# dongle.net
KiCad netlist of a schematic drawn in EAGLE
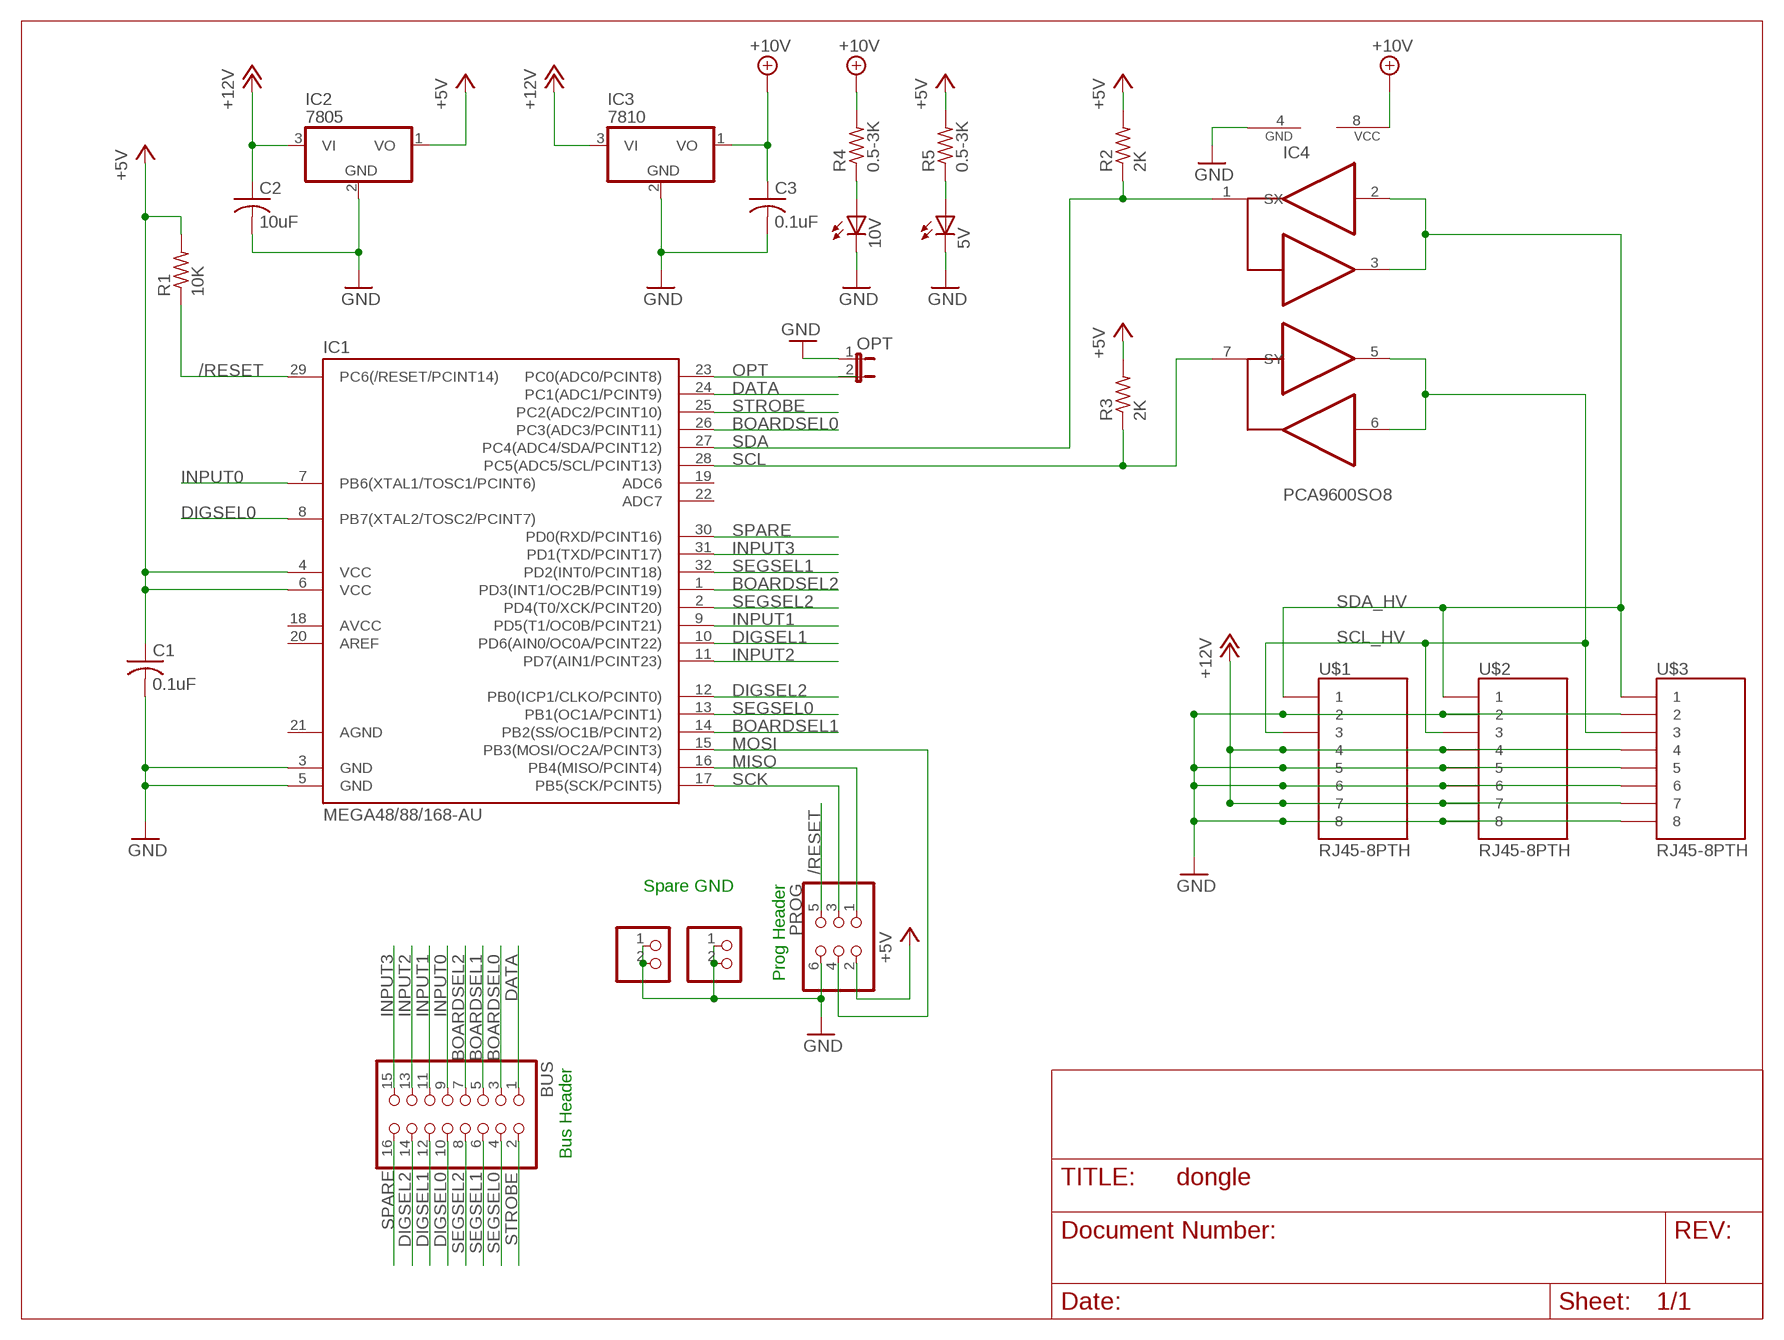
[diagram p0: schematic, sheet 1]

(export (version "E")
  (design (tool "Eeschema 10.0.6"))
  (components
    (comp (ref "5V")
      (value "LED3MM")
      (footprint "eagle-import:LED3MM")
      (libsource (lib "eagle-import") (part "LED3MM"))
    )
    (comp (ref "10V")
      (value "LED3MM")
      (footprint "eagle-import:LED3MM")
      (libsource (lib "eagle-import") (part "LED3MM"))
    )
    (comp (ref "BUS")
      (value "PINHD-2X8")
      (footprint "eagle-import:2X08")
      (libsource (lib "eagle-import") (part "PINHD-2X8"))
    )
    (comp (ref "C1")
      (value "0.1uF")
      (footprint "eagle-import:C025-025X050")
      (libsource (lib "eagle-import") (part "C-US025-025X050"))
    )
    (comp (ref "C2")
      (value "10uF")
      (footprint "eagle-import:C025-025X050")
      (libsource (lib "eagle-import") (part "C-US025-025X050"))
    )
    (comp (ref "C3")
      (value "0.1uF")
      (footprint "eagle-import:C025-025X050")
      (libsource (lib "eagle-import") (part "C-US025-025X050"))
    )
    (comp (ref "GROUND1")
      (value "PINHD-1X2")
      (footprint "eagle-import:1X02")
      (libsource (lib "eagle-import") (part "PINHD-1X2"))
    )
    (comp (ref "GROUND2")
      (value "PINHD-1X2")
      (footprint "eagle-import:1X02")
      (libsource (lib "eagle-import") (part "PINHD-1X2"))
    )
    (comp (ref "IC1")
      (value "MEGA48/88/168-AU")
      (footprint "eagle-import:TQFP32-08")
      (libsource (lib "eagle-import") (part "MEGA48/88/168-AU"))
    )
    (comp (ref "IC2")
      (value "7805")
      (footprint "eagle-import:TO92")
      (libsource (lib "eagle-import") (part "78ZL05"))
    )
    (comp (ref "IC3")
      (value "7810")
      (footprint "eagle-import:TO92")
      (libsource (lib "eagle-import") (part "78ZL05"))
    )
    (comp (ref "IC4")
      (value "PCA9600SO8")
      (footprint "eagle-import:SO08")
      (libsource (lib "eagle-import") (part "PCA9600SO8"))
    )
    (comp (ref "OPT")
      (value "JUMPER-2PTH")
      (footprint "eagle-import:1X02")
      (libsource (lib "eagle-import") (part "JUMPER-2PTH"))
    )
    (comp (ref "PROG")
      (value "PINHD-2X3")
      (footprint "eagle-import:2X03")
      (libsource (lib "eagle-import") (part "PINHD-2X3"))
    )
    (comp (ref "R1")
      (value "10K")
      (footprint "eagle-import:0204_5")
      (libsource (lib "eagle-import") (part "R-US_0204/5"))
    )
    (comp (ref "R2")
      (value "2K")
      (footprint "eagle-import:0204_5")
      (libsource (lib "eagle-import") (part "R-US_0204/5"))
    )
    (comp (ref "R3")
      (value "2K")
      (footprint "eagle-import:0204_5")
      (libsource (lib "eagle-import") (part "R-US_0204/5"))
    )
    (comp (ref "R4")
      (value "0.5-3K")
      (footprint "eagle-import:0204_5")
      (libsource (lib "eagle-import") (part "R-US_0204/5"))
    )
    (comp (ref "R5")
      (value "0.5-3K")
      (footprint "eagle-import:0204_5")
      (libsource (lib "eagle-import") (part "R-US_0204/5"))
    )
    (comp (ref "U$1")
      (value "RJ45-8PTH")
      (footprint "eagle-import:RJ45-8")
      (libsource (lib "eagle-import") (part "RJ45-8PTH"))
    )
    (comp (ref "U$2")
      (value "RJ45-8PTH")
      (footprint "eagle-import:RJ45-8")
      (libsource (lib "eagle-import") (part "RJ45-8PTH"))
    )
    (comp (ref "U$3")
      (value "RJ45-8PTH")
      (footprint "eagle-import:RJ45-8")
      (libsource (lib "eagle-import") (part "RJ45-8PTH"))
    )
  )
  (nets
    (net (code "1") (name "+5V") (class "Default")
      (node (ref "C1") (pin "1") (pinfunction "1_1") (pintype "passive"))
      (node (ref "IC1") (pin "4") (pinfunction "VCC_4") (pintype "power_in"))
      (node (ref "IC1") (pin "6") (pinfunction "VCC_6") (pintype "power_in"))
      (node (ref "IC2") (pin "1") (pinfunction "VO_1") (pintype "passive"))
      (node (ref "PROG") (pin "2") (pinfunction "2_2") (pintype "passive"))
      (node (ref "R1") (pin "2") (pinfunction "2_2") (pintype "passive"))
      (node (ref "R2") (pin "2") (pinfunction "2_2") (pintype "passive"))
      (node (ref "R3") (pin "2") (pinfunction "2_2") (pintype "passive"))
      (node (ref "R5") (pin "2") (pinfunction "2_2") (pintype "passive"))
    )
    (net (code "2") (name "+10V") (class "Default")
      (node (ref "C3") (pin "1") (pinfunction "1_1") (pintype "passive"))
      (node (ref "IC3") (pin "1") (pinfunction "VO_1") (pintype "passive"))
      (node (ref "IC4") (pin "8") (pinfunction "VCC_8") (pintype "power_in"))
      (node (ref "R4") (pin "2") (pinfunction "2_2") (pintype "passive"))
    )
    (net (code "3") (name "+12V") (class "Default")
      (node (ref "C2") (pin "1") (pinfunction "1_1") (pintype "passive"))
      (node (ref "IC2") (pin "3") (pinfunction "VI_3") (pintype "input"))
      (node (ref "IC3") (pin "3") (pinfunction "VI_3") (pintype "input"))
      (node (ref "U$1") (pin "4") (pinfunction "4_4") (pintype "bidirectional"))
      (node (ref "U$1") (pin "7") (pinfunction "7_7") (pintype "bidirectional"))
      (node (ref "U$2") (pin "4") (pinfunction "4_4") (pintype "bidirectional"))
      (node (ref "U$2") (pin "7") (pinfunction "7_7") (pintype "bidirectional"))
      (node (ref "U$3") (pin "4") (pinfunction "4_4") (pintype "bidirectional"))
      (node (ref "U$3") (pin "7") (pinfunction "7_7") (pintype "bidirectional"))
    )
    (net (code "4") (name "/AGND") (class "Default")
      (node (ref "IC1") (pin "21") (pinfunction "AGND_21") (pintype "power_in"))
    )
    (net (code "5") (name "/BOARDSEL0") (class "Default")
      (node (ref "BUS") (pin "3") (pinfunction "3_3") (pintype "passive"))
      (node (ref "IC1") (pin "26") (pinfunction "PC3(ADC3/PCINT11)_26") (pintype "bidirectional"))
    )
    (net (code "6") (name "/BOARDSEL1") (class "Default")
      (node (ref "BUS") (pin "5") (pinfunction "5_5") (pintype "passive"))
      (node (ref "IC1") (pin "14") (pinfunction "PB2(SS/OC1B/PCINT2)_14") (pintype "bidirectional"))
    )
    (net (code "7") (name "/BOARDSEL2") (class "Default")
      (node (ref "BUS") (pin "7") (pinfunction "7_7") (pintype "passive"))
      (node (ref "IC1") (pin "1") (pinfunction "PD3(INT1/OC2B/PCINT19)_1") (pintype "bidirectional"))
    )
    (net (code "8") (name "/DATA") (class "Default")
      (node (ref "BUS") (pin "1") (pinfunction "1_1") (pintype "passive"))
      (node (ref "IC1") (pin "24") (pinfunction "PC1(ADC1/PCINT9)_24") (pintype "bidirectional"))
    )
    (net (code "9") (name "/DIGSEL0") (class "Default")
      (node (ref "BUS") (pin "10") (pinfunction "10_10") (pintype "passive"))
      (node (ref "IC1") (pin "8") (pinfunction "PB7(XTAL2/TOSC2/PCINT7)_8") (pintype "bidirectional"))
    )
    (net (code "10") (name "/DIGSEL1") (class "Default")
      (node (ref "BUS") (pin "12") (pinfunction "12_12") (pintype "passive"))
      (node (ref "IC1") (pin "10") (pinfunction "PD6(AIN0/OC0A/PCINT22)_10") (pintype "bidirectional"))
    )
    (net (code "11") (name "/DIGSEL2") (class "Default")
      (node (ref "BUS") (pin "14") (pinfunction "14_14") (pintype "passive"))
      (node (ref "IC1") (pin "12") (pinfunction "PB0(ICP1/CLKO/PCINT0)_12") (pintype "bidirectional"))
    )
    (net (code "12") (name "/INPUT0") (class "Default")
      (node (ref "BUS") (pin "9") (pinfunction "9_9") (pintype "passive"))
      (node (ref "IC1") (pin "7") (pinfunction "PB6(XTAL1/TOSC1/PCINT6)_7") (pintype "bidirectional"))
    )
    (net (code "13") (name "/INPUT1") (class "Default")
      (node (ref "BUS") (pin "11") (pinfunction "11_11") (pintype "passive"))
      (node (ref "IC1") (pin "9") (pinfunction "PD5(T1/OC0B/PCINT21)_9") (pintype "bidirectional"))
    )
    (net (code "14") (name "/INPUT2") (class "Default")
      (node (ref "BUS") (pin "13") (pinfunction "13_13") (pintype "passive"))
      (node (ref "IC1") (pin "11") (pinfunction "PD7(AIN1/PCINT23)_11") (pintype "bidirectional"))
    )
    (net (code "15") (name "/INPUT3") (class "Default")
      (node (ref "BUS") (pin "15") (pinfunction "15_15") (pintype "passive"))
      (node (ref "IC1") (pin "31") (pinfunction "PD1(TXD/PCINT17)_31") (pintype "bidirectional"))
    )
    (net (code "16") (name "/MISO") (class "Default")
      (node (ref "IC1") (pin "16") (pinfunction "PB4(MISO/PCINT4)_16") (pintype "bidirectional"))
      (node (ref "PROG") (pin "1") (pinfunction "1_1") (pintype "passive"))
    )
    (net (code "17") (name "/MOSI") (class "Default")
      (node (ref "IC1") (pin "15") (pinfunction "PB3(MOSI/OC2A/PCINT3)_15") (pintype "bidirectional"))
      (node (ref "PROG") (pin "4") (pinfunction "4_4") (pintype "passive"))
    )
    (net (code "18") (name "/OPT") (class "Default")
      (node (ref "IC1") (pin "23") (pinfunction "PC0(ADC0/PCINT8)_23") (pintype "bidirectional"))
      (node (ref "OPT") (pin "2") (pinfunction "2_2") (pintype "passive"))
    )
    (net (code "19") (name "/SCK") (class "Default")
      (node (ref "IC1") (pin "17") (pinfunction "PB5(SCK/PCINT5)_17") (pintype "bidirectional"))
      (node (ref "PROG") (pin "3") (pinfunction "3_3") (pintype "passive"))
    )
    (net (code "20") (name "/SCL") (class "Default")
      (node (ref "IC1") (pin "28") (pinfunction "PC5(ADC5/SCL/PCINT13)_28") (pintype "bidirectional"))
      (node (ref "IC4") (pin "7") (pinfunction "SY_7") (pintype "bidirectional"))
      (node (ref "R3") (pin "1") (pinfunction "1_1") (pintype "passive"))
    )
    (net (code "21") (name "/SCL_HV") (class "Default")
      (node (ref "IC4") (pin "5") (pinfunction "TY_5") (pintype "output"))
      (node (ref "IC4") (pin "6") (pinfunction "RY_6") (pintype "input"))
      (node (ref "U$1") (pin "3") (pinfunction "3_3") (pintype "bidirectional"))
      (node (ref "U$2") (pin "3") (pinfunction "3_3") (pintype "bidirectional"))
      (node (ref "U$3") (pin "3") (pinfunction "3_3") (pintype "bidirectional"))
    )
    (net (code "22") (name "/SDA") (class "Default")
      (node (ref "IC1") (pin "27") (pinfunction "PC4(ADC4/SDA/PCINT12)_27") (pintype "bidirectional"))
      (node (ref "IC4") (pin "1") (pinfunction "SX_1") (pintype "bidirectional"))
      (node (ref "R2") (pin "1") (pinfunction "1_1") (pintype "passive"))
    )
    (net (code "23") (name "/SDA_HV") (class "Default")
      (node (ref "IC4") (pin "2") (pinfunction "RX_2") (pintype "input"))
      (node (ref "IC4") (pin "3") (pinfunction "TX_3") (pintype "output"))
      (node (ref "U$1") (pin "1") (pinfunction "1_1") (pintype "bidirectional"))
      (node (ref "U$2") (pin "1") (pinfunction "1_1") (pintype "bidirectional"))
      (node (ref "U$3") (pin "1") (pinfunction "1_1") (pintype "bidirectional"))
    )
    (net (code "24") (name "/SEGSEL0") (class "Default")
      (node (ref "BUS") (pin "4") (pinfunction "4_4") (pintype "passive"))
      (node (ref "IC1") (pin "13") (pinfunction "PB1(OC1A/PCINT1)_13") (pintype "bidirectional"))
    )
    (net (code "25") (name "/SEGSEL1") (class "Default")
      (node (ref "BUS") (pin "6") (pinfunction "6_6") (pintype "passive"))
      (node (ref "IC1") (pin "32") (pinfunction "PD2(INT0/PCINT18)_32") (pintype "bidirectional"))
    )
    (net (code "26") (name "/SEGSEL2") (class "Default")
      (node (ref "BUS") (pin "8") (pinfunction "8_8") (pintype "passive"))
      (node (ref "IC1") (pin "2") (pinfunction "PD4(T0/XCK/PCINT20)_2") (pintype "bidirectional"))
    )
    (net (code "27") (name "/SPARE") (class "Default")
      (node (ref "BUS") (pin "16") (pinfunction "16_16") (pintype "passive"))
      (node (ref "IC1") (pin "30") (pinfunction "PD0(RXD/PCINT16)_30") (pintype "bidirectional"))
    )
    (net (code "28") (name "/STROBE") (class "Default")
      (node (ref "BUS") (pin "2") (pinfunction "2_2") (pintype "passive"))
      (node (ref "IC1") (pin "25") (pinfunction "PC2(ADC2/PCINT10)_25") (pintype "bidirectional"))
    )
    (net (code "29") (name "/{slash}RESET") (class "Default")
      (node (ref "IC1") (pin "29") (pinfunction "PC6(/RESET/PCINT14)_29") (pintype "bidirectional"))
      (node (ref "PROG") (pin "5") (pinfunction "5_5") (pintype "passive"))
      (node (ref "R1") (pin "1") (pinfunction "1_1") (pintype "passive"))
    )
    (net (code "30") (name "GND") (class "Default")
      (node (ref "10V") (pin "K") (pinfunction "C_K") (pintype "passive"))
      (node (ref "5V") (pin "K") (pinfunction "C_K") (pintype "passive"))
      (node (ref "C1") (pin "2") (pinfunction "2_2") (pintype "passive"))
      (node (ref "C2") (pin "2") (pinfunction "2_2") (pintype "passive"))
      (node (ref "C3") (pin "2") (pinfunction "2_2") (pintype "passive"))
      (node (ref "GROUND1") (pin "1") (pinfunction "1_1") (pintype "passive"))
      (node (ref "GROUND1") (pin "2") (pinfunction "2_2") (pintype "passive"))
      (node (ref "GROUND2") (pin "1") (pinfunction "1_1") (pintype "passive"))
      (node (ref "GROUND2") (pin "2") (pinfunction "2_2") (pintype "passive"))
      (node (ref "IC1") (pin "3") (pinfunction "GND_3") (pintype "power_in"))
      (node (ref "IC1") (pin "5") (pinfunction "GND_5") (pintype "power_in"))
      (node (ref "IC2") (pin "2") (pinfunction "GND_2") (pintype "passive"))
      (node (ref "IC3") (pin "2") (pinfunction "GND_2") (pintype "passive"))
      (node (ref "IC4") (pin "4") (pinfunction "GND_4") (pintype "power_in"))
      (node (ref "OPT") (pin "1") (pinfunction "1_1") (pintype "passive"))
      (node (ref "PROG") (pin "6") (pinfunction "6_6") (pintype "passive"))
      (node (ref "U$1") (pin "2") (pinfunction "2_2") (pintype "bidirectional"))
      (node (ref "U$1") (pin "5") (pinfunction "5_5") (pintype "bidirectional"))
      (node (ref "U$1") (pin "6") (pinfunction "6_6") (pintype "bidirectional"))
      (node (ref "U$1") (pin "8") (pinfunction "8_8") (pintype "bidirectional"))
      (node (ref "U$2") (pin "2") (pinfunction "2_2") (pintype "bidirectional"))
      (node (ref "U$2") (pin "5") (pinfunction "5_5") (pintype "bidirectional"))
      (node (ref "U$2") (pin "6") (pinfunction "6_6") (pintype "bidirectional"))
      (node (ref "U$2") (pin "8") (pinfunction "8_8") (pintype "bidirectional"))
      (node (ref "U$3") (pin "2") (pinfunction "2_2") (pintype "bidirectional"))
      (node (ref "U$3") (pin "5") (pinfunction "5_5") (pintype "bidirectional"))
      (node (ref "U$3") (pin "6") (pinfunction "6_6") (pintype "bidirectional"))
      (node (ref "U$3") (pin "8") (pinfunction "8_8") (pintype "bidirectional"))
    )
    (net (code "31") (name "Net-(5V-PadA)") (class "Default")
      (node (ref "5V") (pin "A") (pinfunction "A_A") (pintype "passive"))
      (node (ref "R5") (pin "1") (pinfunction "1_1") (pintype "passive"))
    )
    (net (code "32") (name "Net-(10V-PadA)") (class "Default")
      (node (ref "10V") (pin "A") (pinfunction "A_A") (pintype "passive"))
      (node (ref "R4") (pin "1") (pinfunction "1_1") (pintype "passive"))
    )
    (net (code "33") (name "unconnected-(IC1-ADC6-Pad19)") (class "Default")
      (node (ref "IC1") (pin "19") (pinfunction "ADC6_19") (pintype "passive"))
    )
    (net (code "34") (name "unconnected-(IC1-ADC7-Pad22)") (class "Default")
      (node (ref "IC1") (pin "22") (pinfunction "ADC7_22") (pintype "passive"))
    )
    (net (code "35") (name "unconnected-(IC1-AREF-Pad20)") (class "Default")
      (node (ref "IC1") (pin "20") (pinfunction "AREF_20") (pintype "passive"))
    )
    (net (code "36") (name "unconnected-(IC1-AVCC-Pad18)") (class "Default")
      (node (ref "IC1") (pin "18") (pinfunction "AVCC_18") (pintype "passive"))
    )
  )
)
